# On-Off_Signal_Control.net
KiCad netlist of a schematic drawn in Altium Designer
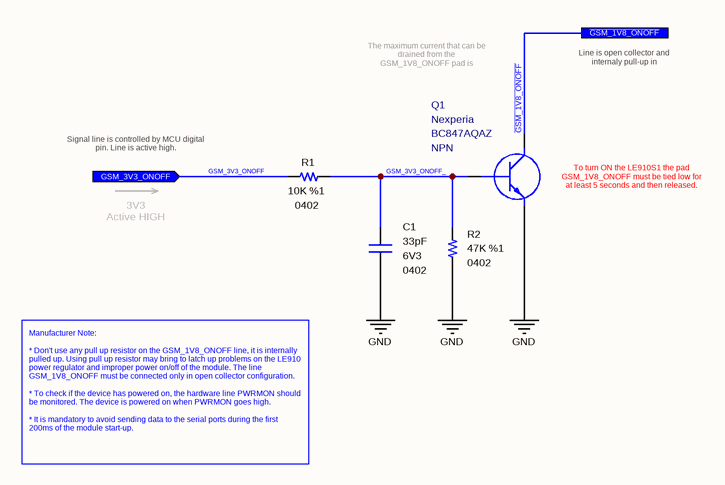
[diagram p0: On-Off Signal Control.SchDoc]

(export (version "E")
  (design (tool "Eeschema 10.0.6"))
  (components
    (comp (ref "C1")
      (value "33pF")
      (footprint "CAPACITOR_0402")
      (description "Capacitor - 33pF [0402] (Ceramic)")
      (fields
        (field (name "CASE") "0402")
        (field (name "VOLTAGE") "6V3")
        (field (name "MANUFACTURER PART NUMBER") "C0402C330J9RACAUTO")
        (field (name "TOLERANCE") "10%")
      )
      (libsource (lib "P101DA_Library") (part "33pF [0402-6V3]"))
    )
    (comp (ref "Q1")
      (value "~")
      (footprint "SOT1215")
      (description "Bipolar NPN Transistors")
      (fields
        (field (name "POLARITY") "NPN")
        (field (name "MANUFACTURER PART NUMBER") "BC847AQAZ")
        (field (name "MANUFACTURER NAME") "Nexperia")
      )
      (libsource (lib "P101DA_Library") (part "BC847"))
    )
    (comp (ref "R1")
      (value "10K")
      (footprint "RESISTOR_0402")
      (description "Thick Film Resistors - SMD 1/16 W 10 Kohms 1%")
      (fields
        (field (name "CASE") "0402")
        (field (name "MANUFACTURER PART NUMBER") "CRCW040210K0FKED")
        (field (name "TOLERANCE") "%1")
      )
      (libsource (lib "P101DA_Library") (part "10K"))
    )
    (comp (ref "R2")
      (value "47K")
      (footprint "RESISTOR_0402")
      (description "Thick Film Resistors - SMD 1/16 W 47 Kohms 1%")
      (fields
        (field (name "CASE") "0402")
        (field (name "MANUFACTURER PART NUMBER") "CRCW040247K0FKED")
        (field (name "TOLERANCE") "%1")
      )
      (libsource (lib "P101DA_Library") (part "47K"))
    )
  )
  (nets
    (net (code "1") (name "/GSM_3V3_ONOFF") (class "Default")
      (node (ref "R1") (pin "2") (pinfunction "2_2") (pintype "passive"))
    )
    (net (code "2") (name "/GSM_3V3_ONOFF_") (class "Default")
      (node (ref "C1") (pin "2") (pinfunction "2_2") (pintype "passive"))
      (node (ref "Q1") (pin "1") (pinfunction "B_1") (pintype "passive"))
      (node (ref "R1") (pin "1") (pinfunction "1_1") (pintype "passive"))
      (node (ref "R2") (pin "2") (pinfunction "2_2") (pintype "passive"))
    )
    (net (code "3") (name "/~{GSM_1V8_ONOFF}") (class "Default")
      (node (ref "Q1") (pin "3") (pinfunction "C_3") (pintype "passive"))
    )
    (net (code "4") (name "GND") (class "Default")
      (node (ref "C1") (pin "1") (pinfunction "1_1") (pintype "passive"))
      (node (ref "Q1") (pin "2") (pinfunction "E_2") (pintype "passive"))
      (node (ref "R2") (pin "1") (pinfunction "1_1") (pintype "passive"))
    )
  )
)
